# beeshield.net
KiCad netlist of a schematic drawn in EAGLE
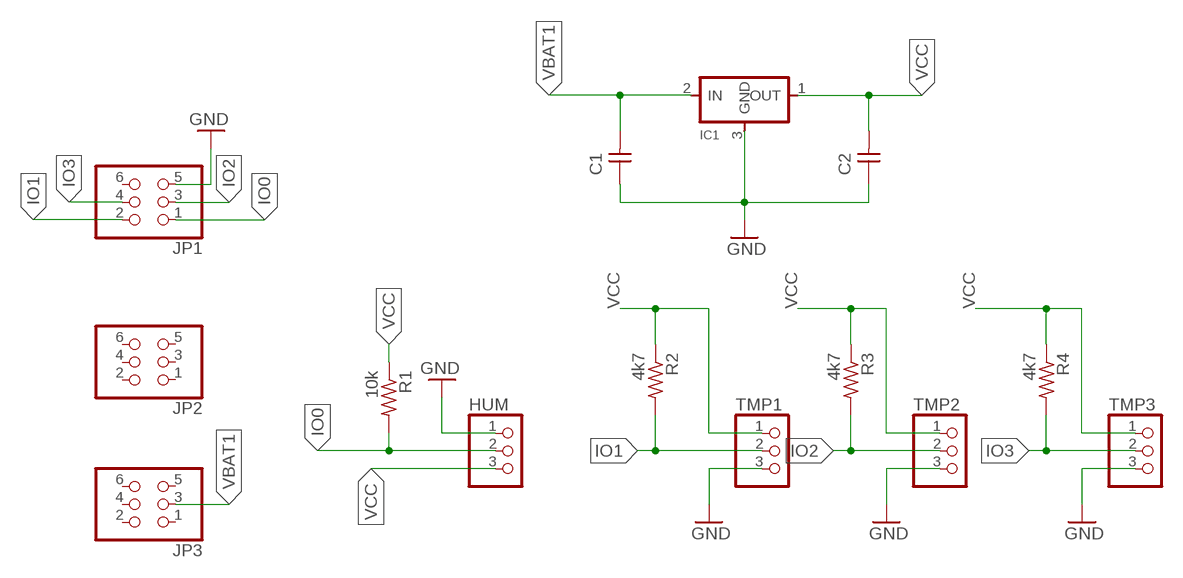
[diagram p0: schematic, sheet 1]

(export (version "E")
  (design (tool "Eeschema 10.0.6"))
  (components
    (comp (ref "C1")
      (value "UNPOLARIZED_CAPACITOR1206")
      (footprint "eagle-import:1206")
      (libsource (lib "eagle-import") (part "UNPOLARIZED_CAPACITOR1206"))
    )
    (comp (ref "C2")
      (value "UNPOLARIZED_CAPACITOR1206")
      (footprint "eagle-import:1206")
      (libsource (lib "eagle-import") (part "UNPOLARIZED_CAPACITOR1206"))
    )
    (comp (ref "HUM")
      (value "PINHD-1X3")
      (footprint "eagle-import:1X03")
      (libsource (lib "eagle-import") (part "PINHD-1X3"))
    )
    (comp (ref "IC1")
      (value "REGULATORSOT23")
      (footprint "eagle-import:SOT23")
      (libsource (lib "eagle-import") (part "REGULATORSOT23"))
    )
    (comp (ref "JP1")
      (value "PINHD-2X3-SMD")
      (footprint "eagle-import:2X03SMD")
      (libsource (lib "eagle-import") (part "PINHD-2X3-SMD"))
    )
    (comp (ref "JP2")
      (value "PINHD-2X3-SMD")
      (footprint "eagle-import:2X03SMD")
      (libsource (lib "eagle-import") (part "PINHD-2X3-SMD"))
    )
    (comp (ref "JP3")
      (value "PINHD-2X3-SMD")
      (footprint "eagle-import:2X03SMD")
      (libsource (lib "eagle-import") (part "PINHD-2X3-SMD"))
    )
    (comp (ref "R1")
      (value "10k")
      (footprint "eagle-import:1206")
      (libsource (lib "eagle-import") (part "RESISTOR1206"))
    )
    (comp (ref "R2")
      (value "4k7")
      (footprint "eagle-import:1206")
      (libsource (lib "eagle-import") (part "RESISTOR1206"))
    )
    (comp (ref "R3")
      (value "4k7")
      (footprint "eagle-import:1206")
      (libsource (lib "eagle-import") (part "RESISTOR1206"))
    )
    (comp (ref "R4")
      (value "4k7")
      (footprint "eagle-import:1206")
      (libsource (lib "eagle-import") (part "RESISTOR1206"))
    )
    (comp (ref "TMP1")
      (value "PINHD-1X3")
      (footprint "eagle-import:1X03")
      (libsource (lib "eagle-import") (part "PINHD-1X3"))
    )
    (comp (ref "TMP2")
      (value "PINHD-1X3")
      (footprint "eagle-import:1X03")
      (libsource (lib "eagle-import") (part "PINHD-1X3"))
    )
    (comp (ref "TMP3")
      (value "PINHD-1X3")
      (footprint "eagle-import:1X03")
      (libsource (lib "eagle-import") (part "PINHD-1X3"))
    )
  )
  (nets
    (net (code "1") (name "GND") (class "Default")
      (node (ref "C1") (pin "1") (pinfunction "1_1") (pintype "passive"))
      (node (ref "C2") (pin "1") (pinfunction "1_1") (pintype "passive"))
      (node (ref "HUM") (pin "1") (pinfunction "1_1") (pintype "passive"))
      (node (ref "IC1") (pin "3") (pinfunction "GND_3") (pintype "bidirectional"))
      (node (ref "JP1") (pin "5") (pinfunction "5_5") (pintype "passive"))
      (node (ref "TMP1") (pin "3") (pinfunction "3_3") (pintype "passive"))
      (node (ref "TMP2") (pin "3") (pinfunction "3_3") (pintype "passive"))
      (node (ref "TMP3") (pin "3") (pinfunction "3_3") (pintype "passive"))
    )
    (net (code "2") (name "IO0") (class "Default")
      (node (ref "HUM") (pin "2") (pinfunction "2_2") (pintype "passive"))
      (node (ref "JP1") (pin "1") (pinfunction "1_1") (pintype "passive"))
      (node (ref "R1") (pin "2") (pinfunction "2_2") (pintype "passive"))
    )
    (net (code "3") (name "IO1") (class "Default")
      (node (ref "JP1") (pin "2") (pinfunction "2_2") (pintype "passive"))
      (node (ref "R2") (pin "2") (pinfunction "2_2") (pintype "passive"))
      (node (ref "TMP1") (pin "2") (pinfunction "2_2") (pintype "passive"))
    )
    (net (code "4") (name "IO2") (class "Default")
      (node (ref "JP1") (pin "3") (pinfunction "3_3") (pintype "passive"))
      (node (ref "R3") (pin "2") (pinfunction "2_2") (pintype "passive"))
      (node (ref "TMP2") (pin "2") (pinfunction "2_2") (pintype "passive"))
    )
    (net (code "5") (name "IO3") (class "Default")
      (node (ref "JP1") (pin "4") (pinfunction "4_4") (pintype "passive"))
      (node (ref "R4") (pin "2") (pinfunction "2_2") (pintype "passive"))
      (node (ref "TMP3") (pin "2") (pinfunction "2_2") (pintype "passive"))
    )
    (net (code "6") (name "VBAT1") (class "Default")
      (node (ref "C1") (pin "2") (pinfunction "2_2") (pintype "passive"))
      (node (ref "IC1") (pin "2") (pinfunction "IN_2") (pintype "bidirectional"))
      (node (ref "JP3") (pin "3") (pinfunction "3_3") (pintype "passive"))
    )
    (net (code "7") (name "VCC") (class "Default")
      (node (ref "C2") (pin "2") (pinfunction "2_2") (pintype "passive"))
      (node (ref "HUM") (pin "3") (pinfunction "3_3") (pintype "passive"))
      (node (ref "IC1") (pin "1") (pinfunction "OUT_1") (pintype "bidirectional"))
      (node (ref "R1") (pin "1") (pinfunction "1_1") (pintype "passive"))
      (node (ref "R2") (pin "1") (pinfunction "1_1") (pintype "passive"))
      (node (ref "R3") (pin "1") (pinfunction "1_1") (pintype "passive"))
      (node (ref "R4") (pin "1") (pinfunction "1_1") (pintype "passive"))
      (node (ref "TMP1") (pin "1") (pinfunction "1_1") (pintype "passive"))
      (node (ref "TMP2") (pin "1") (pinfunction "1_1") (pintype "passive"))
      (node (ref "TMP3") (pin "1") (pinfunction "1_1") (pintype "passive"))
    )
    (net (code "8") (name "unconnected-(JP1-Pad6)") (class "Default")
      (node (ref "JP1") (pin "6") (pinfunction "6_6") (pintype "passive"))
    )
    (net (code "9") (name "unconnected-(JP2-Pad1)") (class "Default")
      (node (ref "JP2") (pin "1") (pinfunction "1_1") (pintype "passive"))
    )
    (net (code "10") (name "unconnected-(JP2-Pad2)") (class "Default")
      (node (ref "JP2") (pin "2") (pinfunction "2_2") (pintype "passive"))
    )
    (net (code "11") (name "unconnected-(JP2-Pad3)") (class "Default")
      (node (ref "JP2") (pin "3") (pinfunction "3_3") (pintype "passive"))
    )
    (net (code "12") (name "unconnected-(JP2-Pad4)") (class "Default")
      (node (ref "JP2") (pin "4") (pinfunction "4_4") (pintype "passive"))
    )
    (net (code "13") (name "unconnected-(JP2-Pad5)") (class "Default")
      (node (ref "JP2") (pin "5") (pinfunction "5_5") (pintype "passive"))
    )
    (net (code "14") (name "unconnected-(JP2-Pad6)") (class "Default")
      (node (ref "JP2") (pin "6") (pinfunction "6_6") (pintype "passive"))
    )
    (net (code "15") (name "unconnected-(JP3-Pad1)") (class "Default")
      (node (ref "JP3") (pin "1") (pinfunction "1_1") (pintype "passive"))
    )
    (net (code "16") (name "unconnected-(JP3-Pad2)") (class "Default")
      (node (ref "JP3") (pin "2") (pinfunction "2_2") (pintype "passive"))
    )
    (net (code "17") (name "unconnected-(JP3-Pad4)") (class "Default")
      (node (ref "JP3") (pin "4") (pinfunction "4_4") (pintype "passive"))
    )
    (net (code "18") (name "unconnected-(JP3-Pad5)") (class "Default")
      (node (ref "JP3") (pin "5") (pinfunction "5_5") (pintype "passive"))
    )
    (net (code "19") (name "unconnected-(JP3-Pad6)") (class "Default")
      (node (ref "JP3") (pin "6") (pinfunction "6_6") (pintype "passive"))
    )
  )
)
